# offzone-addon-s7-easyeda-sheet.net
KiCad netlist of a schematic drawn in EasyEDA
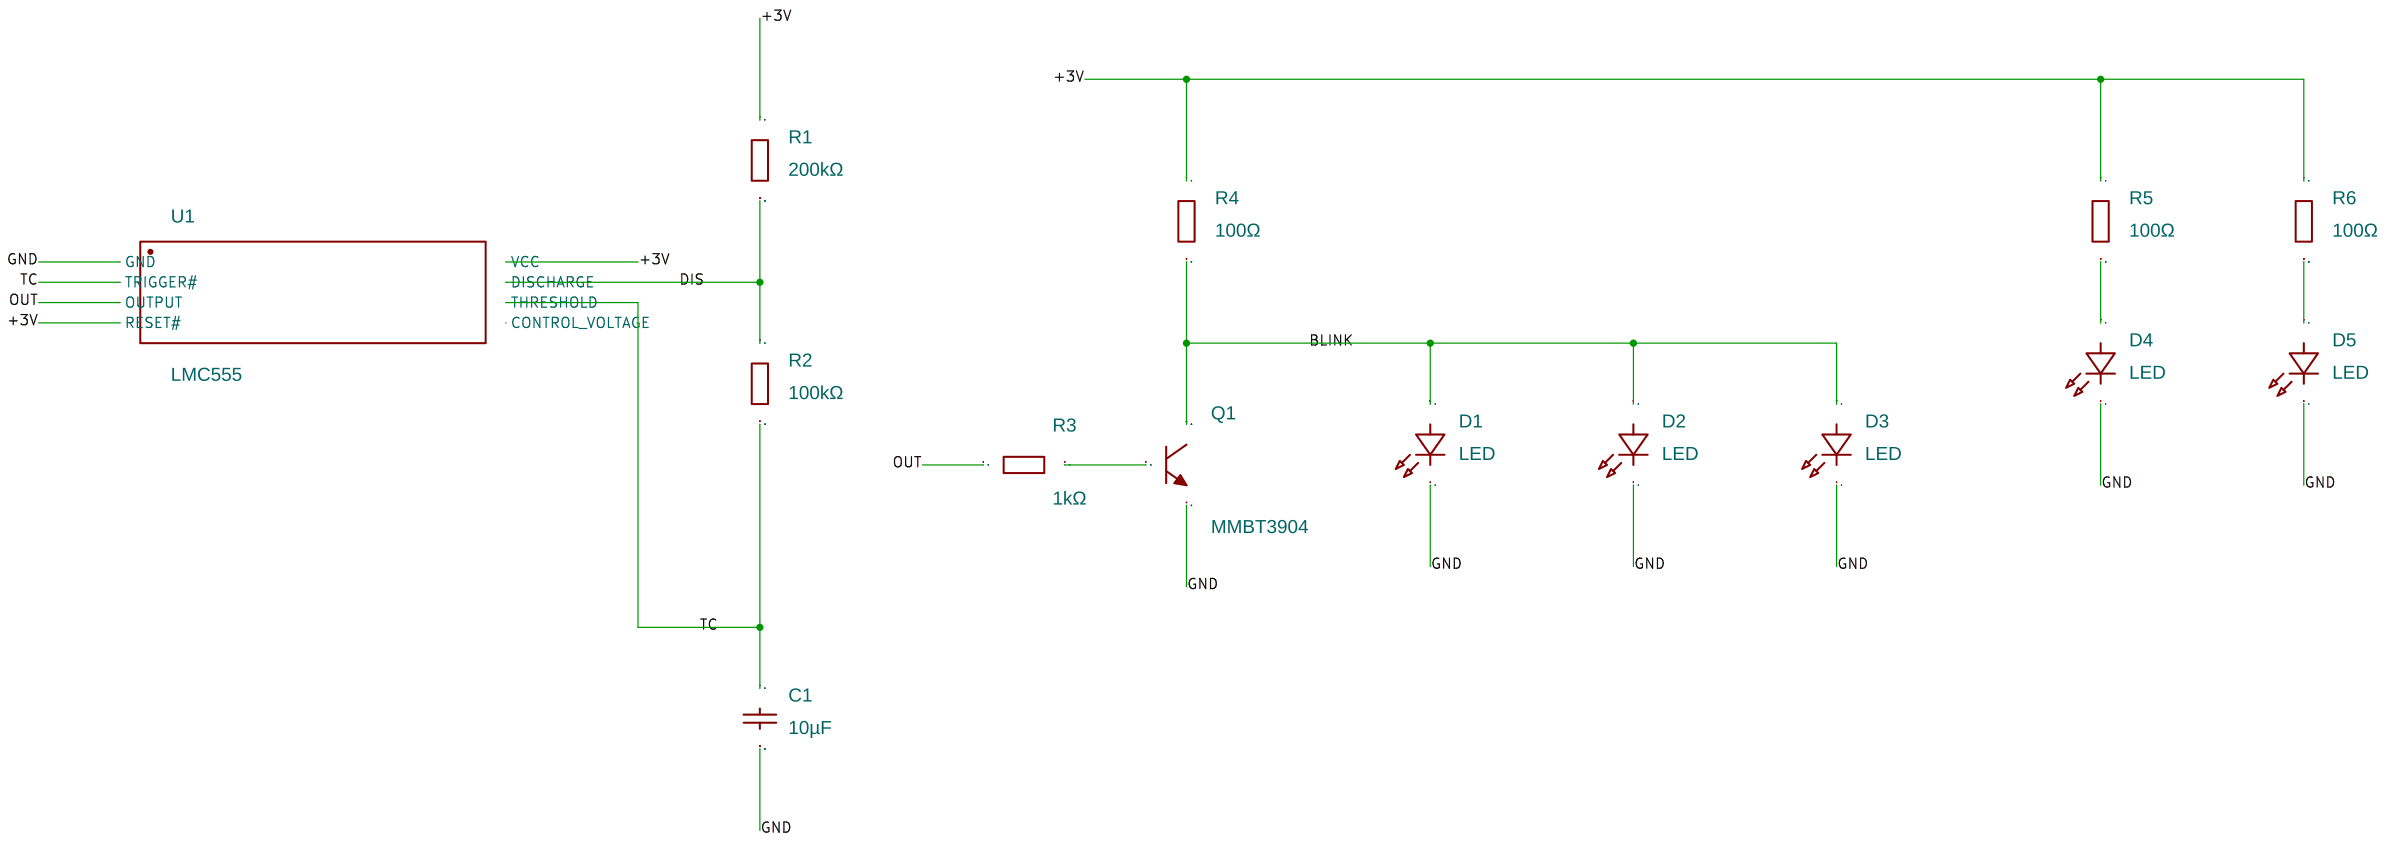
[diagram p0: schematic sheet]

(export (version "E")
  (design (tool "Eeschema 10.0.6"))
  (components
    (comp (ref "C1")
      (value "10µF")
      (fields
        (field (name "BOM_Manufacturer Part") "CL21A106KOQNNNE")
        (field (name "BOM_Supplier Part") "C1713")
      )
      (libsource (lib "") (part "CL21A106KOQNNNE"))
    )
    (comp (ref "D1")
      (value "LED")
      (fields
        (field (name "BOM_Manufacturer Part") "17-21/R6C-AQ2R2B/4T")
        (field (name "BOM_Supplier Part") "C2971979")
      )
      (libsource (lib "") (part "17-21/R6C-AQ2R2B/4T"))
    )
    (comp (ref "D2")
      (value "LED")
      (fields
        (field (name "BOM_Manufacturer Part") "17-21/R6C-AQ2R2B/4T")
        (field (name "BOM_Supplier Part") "C2971979")
      )
      (libsource (lib "") (part "17-21/R6C-AQ2R2B/4T"))
    )
    (comp (ref "D3")
      (value "LED")
      (fields
        (field (name "BOM_Manufacturer Part") "17-21/R6C-AQ2R2B/4T")
        (field (name "BOM_Supplier Part") "C2971979")
      )
      (libsource (lib "") (part "17-21/R6C-AQ2R2B/4T"))
    )
    (comp (ref "D4")
      (value "LED")
      (fields
        (field (name "BOM_Manufacturer Part") "17-21/R6C-AQ2R2B/4T")
        (field (name "BOM_Supplier Part") "C2971979")
      )
      (libsource (lib "") (part "17-21/R6C-AQ2R2B/4T"))
    )
    (comp (ref "D5")
      (value "LED")
      (fields
        (field (name "BOM_Manufacturer Part") "17-21/R6C-AQ2R2B/4T")
        (field (name "BOM_Supplier Part") "C2971979")
      )
      (libsource (lib "") (part "17-21/R6C-AQ2R2B/4T"))
    )
    (comp (ref "Q1")
      (value "MMBT3904")
      (fields
        (field (name "BOM_Manufacturer Part") "MMBT3904LT1G")
        (field (name "BOM_Supplier Part") "C81464")
      )
      (libsource (lib "") (part "MMBT3904LT1G"))
    )
    (comp (ref "R1")
      (value "200kΩ")
      (fields
        (field (name "BOM_Manufacturer Part") "0603WAF2003T5E")
        (field (name "BOM_Supplier Part") "C25811")
      )
      (libsource (lib "") (part "0603WAF2003T5E"))
    )
    (comp (ref "R2")
      (value "100kΩ")
      (fields
        (field (name "BOM_Manufacturer Part") "0603WAF1003T5E")
        (field (name "BOM_Supplier Part") "C25803")
      )
      (libsource (lib "") (part "0603WAF1003T5E"))
    )
    (comp (ref "R3")
      (value "1kΩ")
      (fields
        (field (name "BOM_Manufacturer Part") "0603WAF1001T5E")
        (field (name "BOM_Supplier Part") "C21190")
      )
      (libsource (lib "") (part "0603WAF1001T5E"))
    )
    (comp (ref "R4")
      (value "100Ω")
      (fields
        (field (name "BOM_Manufacturer Part") "RC0603FR-07100RL")
        (field (name "BOM_Supplier Part") "C105588")
      )
      (libsource (lib "") (part "RC0603FR-07100RL"))
    )
    (comp (ref "R5")
      (value "100Ω")
      (fields
        (field (name "BOM_Manufacturer Part") "RC0603FR-07100RL")
        (field (name "BOM_Supplier Part") "C105588")
      )
      (libsource (lib "") (part "RC0603FR-07100RL"))
    )
    (comp (ref "R6")
      (value "100Ω")
      (fields
        (field (name "BOM_Manufacturer Part") "RC0603FR-07100RL")
        (field (name "BOM_Supplier Part") "C105588")
      )
      (libsource (lib "") (part "RC0603FR-07100RL"))
    )
    (comp (ref "U1")
      (value "LMC555")
      (fields
        (field (name "BOM_Manufacturer Part") "LMC555M/TR")
        (field (name "BOM_Supplier Part") "C356725")
      )
      (libsource (lib "") (part "LMC555M/TR"))
    )
  )
  (nets
    (net (code "1") (name "/+3V") (class "Default")
      (node (ref "R1") (pin "1") (pinfunction "1_1") (pintype "input"))
      (node (ref "R4") (pin "1") (pinfunction "1_1") (pintype "input"))
      (node (ref "R5") (pin "1") (pinfunction "1_1") (pintype "input"))
      (node (ref "R6") (pin "1") (pinfunction "1_1") (pintype "input"))
      (node (ref "U1") (pin "4") (pinfunction "RESET#_4") (pintype "unspecified"))
      (node (ref "U1") (pin "8") (pinfunction "VCC_8") (pintype "unspecified"))
    )
    (net (code "2") (name "/BLINK") (class "Default")
      (node (ref "D1") (pin "2") (pinfunction "A_2") (pintype "unspecified"))
      (node (ref "D2") (pin "2") (pinfunction "A_2") (pintype "unspecified"))
      (node (ref "D3") (pin "2") (pinfunction "A_2") (pintype "unspecified"))
      (node (ref "Q1") (pin "3") (pinfunction "3_3") (pintype "input"))
      (node (ref "R4") (pin "2") (pinfunction "2_2") (pintype "input"))
    )
    (net (code "3") (name "/DIS") (class "Default")
      (node (ref "R1") (pin "2") (pinfunction "2_2") (pintype "input"))
      (node (ref "R2") (pin "1") (pinfunction "1_1") (pintype "input"))
      (node (ref "U1") (pin "7") (pinfunction "DISCHARGE_7") (pintype "unspecified"))
    )
    (net (code "4") (name "/GND") (class "Default")
      (node (ref "C1") (pin "2") (pinfunction "2_2") (pintype "input"))
      (node (ref "D1") (pin "1") (pinfunction "K_1") (pintype "unspecified"))
      (node (ref "D2") (pin "1") (pinfunction "K_1") (pintype "unspecified"))
      (node (ref "D3") (pin "1") (pinfunction "K_1") (pintype "unspecified"))
      (node (ref "D4") (pin "1") (pinfunction "K_1") (pintype "unspecified"))
      (node (ref "D5") (pin "1") (pinfunction "K_1") (pintype "unspecified"))
      (node (ref "Q1") (pin "2") (pinfunction "2_2") (pintype "input"))
      (node (ref "U1") (pin "1") (pinfunction "GND_1") (pintype "unspecified"))
    )
    (net (code "5") (name "/OUT") (class "Default")
      (node (ref "R3") (pin "1") (pinfunction "1_1") (pintype "input"))
      (node (ref "U1") (pin "3") (pinfunction "OUTPUT_3") (pintype "unspecified"))
    )
    (net (code "6") (name "/TC") (class "Default")
      (node (ref "C1") (pin "1") (pinfunction "1_1") (pintype "input"))
      (node (ref "R2") (pin "2") (pinfunction "2_2") (pintype "input"))
      (node (ref "U1") (pin "2") (pinfunction "TRIGGER#_2") (pintype "unspecified"))
      (node (ref "U1") (pin "6") (pinfunction "THRESHOLD_6") (pintype "unspecified"))
    )
    (net (code "7") (name "Net-(D4-A)") (class "Default")
      (node (ref "D4") (pin "2") (pinfunction "A_2") (pintype "unspecified"))
      (node (ref "R5") (pin "2") (pinfunction "2_2") (pintype "input"))
    )
    (net (code "8") (name "Net-(D5-A)") (class "Default")
      (node (ref "D5") (pin "2") (pinfunction "A_2") (pintype "unspecified"))
      (node (ref "R6") (pin "2") (pinfunction "2_2") (pintype "input"))
    )
    (net (code "9") (name "Net-(Q1-Pad1)") (class "Default")
      (node (ref "Q1") (pin "1") (pinfunction "1_1") (pintype "input"))
      (node (ref "R3") (pin "2") (pinfunction "2_2") (pintype "input"))
    )
    (net (code "10") (name "unconnected-(U1-CONTROL_VOLTAGE-Pad5)") (class "Default")
      (node (ref "U1") (pin "5") (pinfunction "CONTROL_VOLTAGE_5") (pintype "unspecified"))
    )
  )
)
